# Project_Embedded_Lap_Counting.net
KiCad netlist of a schematic drawn in EAGLE
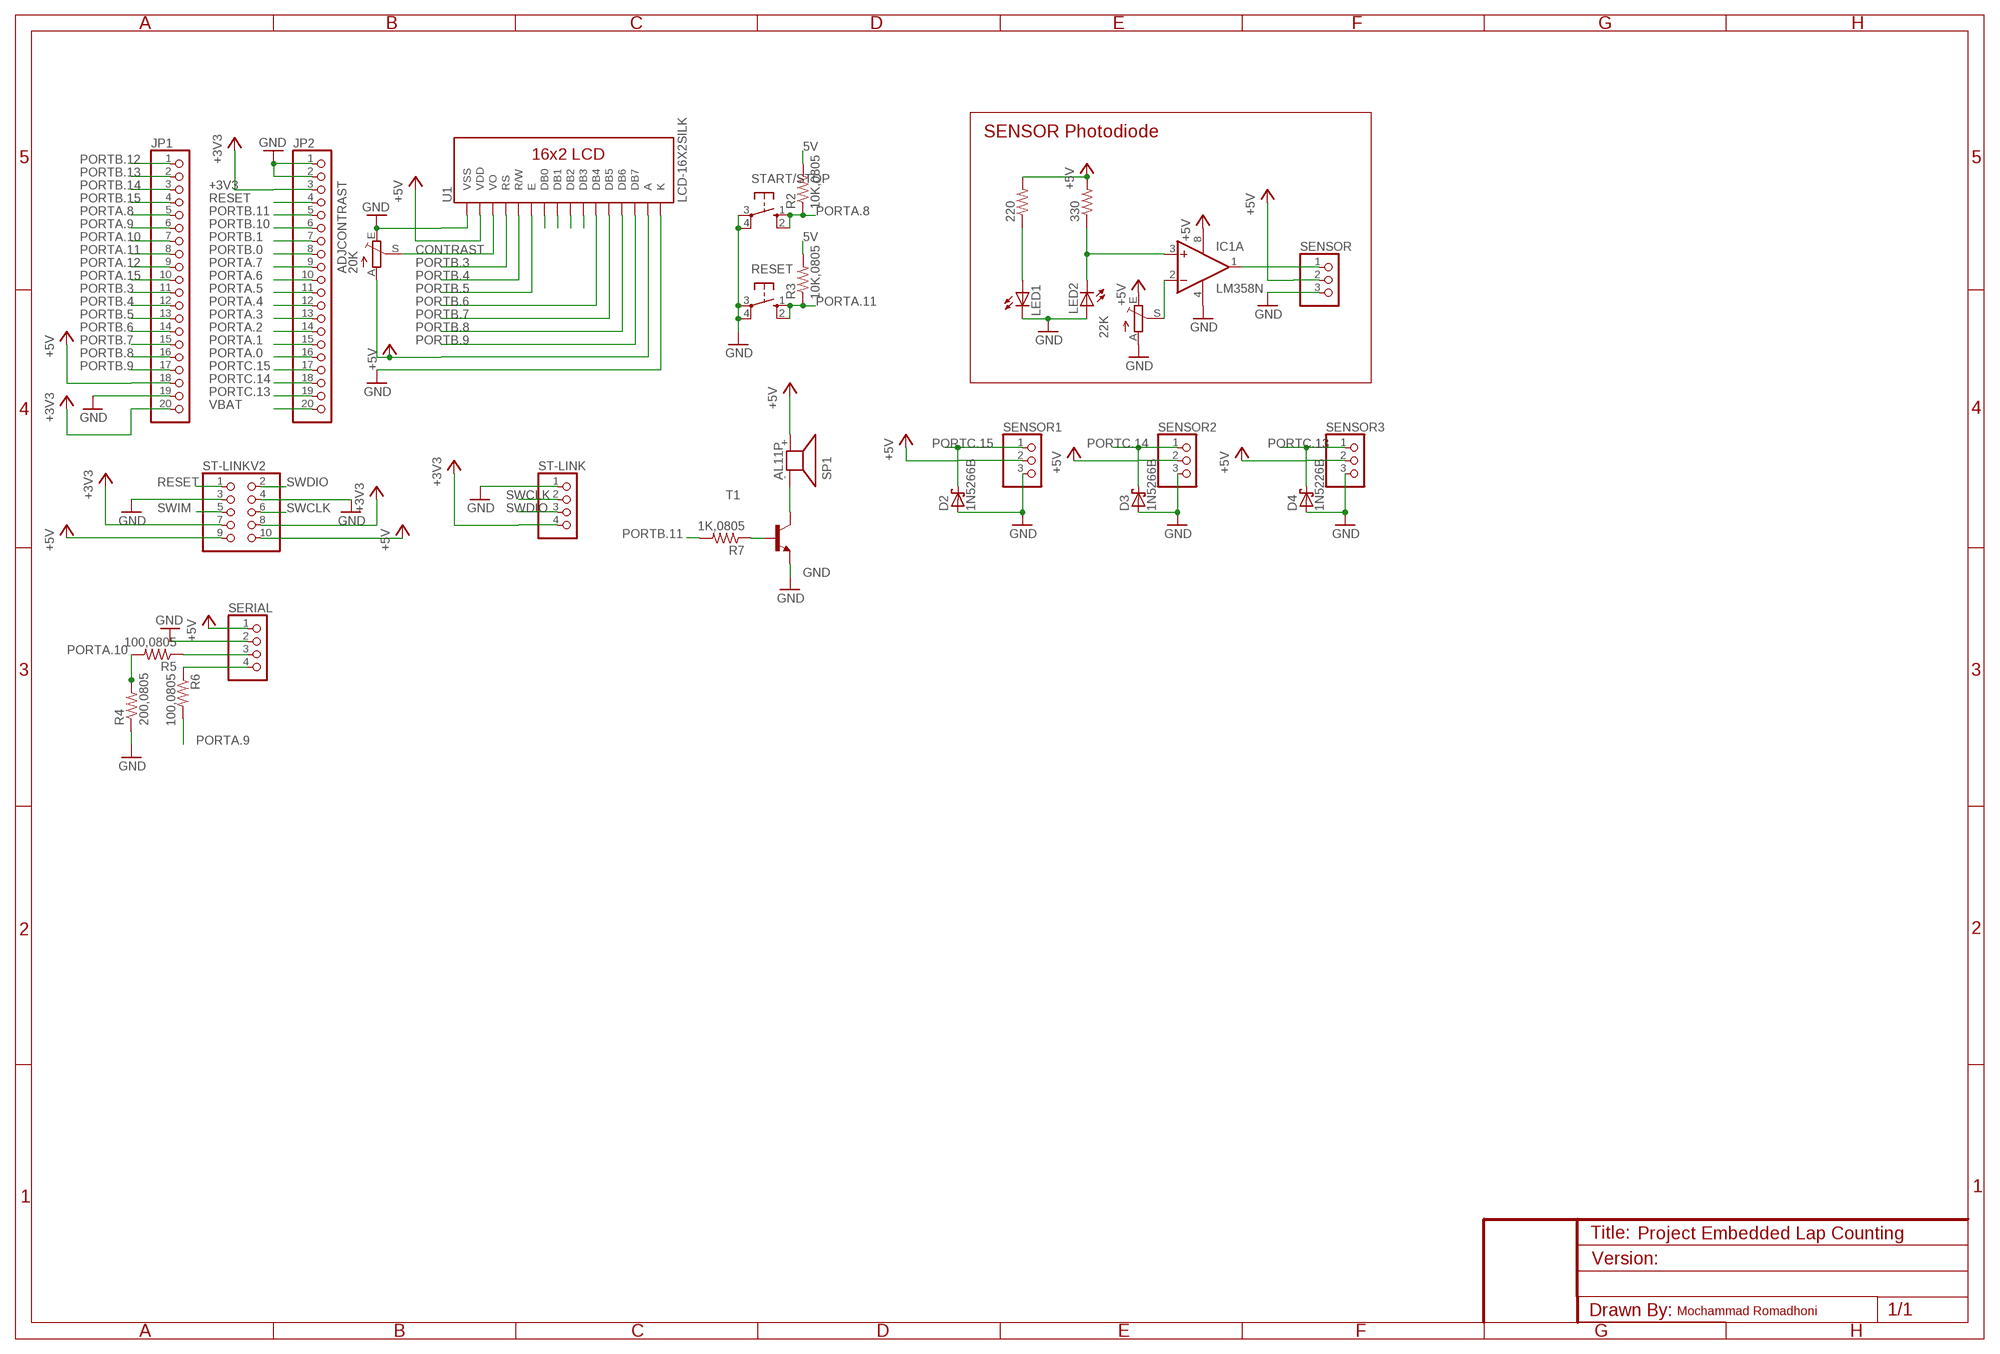
[diagram p0: schematic, sheet 1]

(export (version "E")
  (design (tool "Eeschema 10.0.6"))
  (components
    (comp (ref "22K")
      (value "TRIM_EU-CA6V")
      (footprint "eagle-import:CA6V")
      (libsource (lib "eagle-import") (part "TRIM_EU-CA6V"))
    )
    (comp (ref "220")
      (value "R-US_0204/7")
      (footprint "eagle-import:0204_7")
      (libsource (lib "eagle-import") (part "R-US_0204/7"))
    )
    (comp (ref "330")
      (value "R-US_0204/7")
      (footprint "eagle-import:0204_7")
      (libsource (lib "eagle-import") (part "R-US_0204/7"))
    )
    (comp (ref "ADJCONTRAST")
      (value "20K")
      (footprint "eagle-import:CA6V")
      (libsource (lib "eagle-import") (part "TRIM_EU-CA6V"))
    )
    (comp (ref "D2")
      (value "1N5266B")
      (footprint "eagle-import:DO35-10")
      (libsource (lib "eagle-import") (part "BAT42"))
    )
    (comp (ref "D3")
      (value "1N5266B")
      (footprint "eagle-import:DO35-10")
      (libsource (lib "eagle-import") (part "BAT42"))
    )
    (comp (ref "D4")
      (value "1N5226B")
      (footprint "eagle-import:DO35-10")
      (libsource (lib "eagle-import") (part "BAT42"))
    )
    (comp (ref "IC1")
      (value "LM358N")
      (footprint "eagle-import:DIL08")
      (libsource (lib "eagle-import") (part "LM358N"))
    )
    (comp (ref "JP1")
      (value "PINHD-1X20")
      (footprint "eagle-import:1X20")
      (libsource (lib "eagle-import") (part "PINHD-1X20"))
    )
    (comp (ref "JP2")
      (value "PINHD-1X20")
      (footprint "eagle-import:1X20")
      (libsource (lib "eagle-import") (part "PINHD-1X20"))
    )
    (comp (ref "LED1")
      (value "LED3MM")
      (footprint "eagle-import:LED3MM")
      (libsource (lib "eagle-import") (part "LED3MM"))
    )
    (comp (ref "LED2")
      (value "LED3MM")
      (footprint "eagle-import:LED3MM")
      (libsource (lib "eagle-import") (part "LED3MM"))
    )
    (comp (ref "R2")
      (value "10K,0805")
      (footprint "eagle-import:M0805")
      (libsource (lib "eagle-import") (part "R-US_M0805"))
    )
    (comp (ref "R3")
      (value "10K,0805")
      (footprint "eagle-import:M0805")
      (libsource (lib "eagle-import") (part "R-US_M0805"))
    )
    (comp (ref "R4")
      (value "200,0805")
      (footprint "eagle-import:M0805")
      (libsource (lib "eagle-import") (part "R-US_M0805"))
    )
    (comp (ref "R5")
      (value "100,0805")
      (footprint "eagle-import:M0805")
      (libsource (lib "eagle-import") (part "R-US_M0805"))
    )
    (comp (ref "R6")
      (value "100,0805")
      (footprint "eagle-import:M0805")
      (libsource (lib "eagle-import") (part "R-US_M0805"))
    )
    (comp (ref "R7")
      (value "1K,0805")
      (footprint "eagle-import:M0805")
      (libsource (lib "eagle-import") (part "R-US_M0805"))
    )
    (comp (ref "RESET")
      (value "40-XX")
      (footprint "eagle-import:B3F-40XX")
      (fields (field (name "MF") "OMRON COMPONENTS USA") (field (name "MPN") "B3F-4000"))
      (libsource (lib "eagle-import") (part "40-XX"))
    )
    (comp (ref "SENSOR")
      (value "PINHD-1X3")
      (footprint "eagle-import:1X03")
      (libsource (lib "eagle-import") (part "PINHD-1X3"))
    )
    (comp (ref "SENSOR1")
      (value "PINHD-1X3")
      (footprint "eagle-import:1X03")
      (libsource (lib "eagle-import") (part "PINHD-1X3"))
    )
    (comp (ref "SENSOR2")
      (value "PINHD-1X3")
      (footprint "eagle-import:1X03")
      (libsource (lib "eagle-import") (part "PINHD-1X3"))
    )
    (comp (ref "SENSOR3")
      (value "PINHD-1X3")
      (footprint "eagle-import:1X03")
      (libsource (lib "eagle-import") (part "PINHD-1X3"))
    )
    (comp (ref "SERIAL")
      (value "PINHD-1X4")
      (footprint "eagle-import:1X04")
      (libsource (lib "eagle-import") (part "PINHD-1X4"))
    )
    (comp (ref "SP1")
      (value "AL11P")
      (footprint "eagle-import:AL11P")
      (libsource (lib "eagle-import") (part "AL11P"))
    )
    (comp (ref "ST-LINK")
      (value "PINHD-1X4")
      (footprint "eagle-import:1X04")
      (libsource (lib "eagle-import") (part "PINHD-1X4"))
    )
    (comp (ref "ST-LINKV2")
      (value "PINHD-2X5")
      (footprint "eagle-import:2X05")
      (libsource (lib "eagle-import") (part "PINHD-2X5"))
    )
    (comp (ref "START/STOP")
      (value "40-XX")
      (footprint "eagle-import:B3F-40XX")
      (fields (field (name "MF") "OMRON COMPONENTS USA") (field (name "MPN") "B3F-4000"))
      (libsource (lib "eagle-import") (part "40-XX"))
    )
    (comp (ref "T1")
      (value "-NPN-SOT23-EBC")
      (footprint "eagle-import:SOT23-EBC")
      (libsource (lib "eagle-import") (part "-NPN-SOT23-EBC"))
    )
    (comp (ref "U1")
      (value "LCD-16X2SILK")
      (footprint "eagle-import:LCD-16X2")
      (libsource (lib "eagle-import") (part "LCD-16X2SILK"))
    )
  )
  (nets
    (net (code "1") (name "+3V3") (class "Default")
      (node (ref "JP1") (pin "20") (pinfunction "20_20") (pintype "passive"))
      (node (ref "JP2") (pin "3") (pinfunction "3_3") (pintype "passive"))
      (node (ref "ST-LINK") (pin "4") (pinfunction "4_4") (pintype "passive"))
      (node (ref "ST-LINKV2") (pin "7") (pinfunction "7_7") (pintype "passive"))
      (node (ref "ST-LINKV2") (pin "8") (pinfunction "8_8") (pintype "passive"))
    )
    (net (code "2") (name "+5V") (class "Default")
      (node (ref "220") (pin "2") (pinfunction "2_2") (pintype "passive"))
      (node (ref "22K") (pin "E") (pinfunction "E_E") (pintype "passive"))
      (node (ref "330") (pin "2") (pinfunction "2_2") (pintype "passive"))
      (node (ref "ADJCONTRAST") (pin "A") (pinfunction "A_A") (pintype "passive"))
      (node (ref "IC1") (pin "8") (pinfunction "V+_8") (pintype "power_in"))
      (node (ref "JP1") (pin "18") (pinfunction "18_18") (pintype "passive"))
      (node (ref "SENSOR") (pin "2") (pinfunction "2_2") (pintype "passive"))
      (node (ref "SENSOR1") (pin "2") (pinfunction "2_2") (pintype "passive"))
      (node (ref "SENSOR2") (pin "2") (pinfunction "2_2") (pintype "passive"))
      (node (ref "SENSOR3") (pin "2") (pinfunction "2_2") (pintype "passive"))
      (node (ref "SERIAL") (pin "1") (pinfunction "1_1") (pintype "passive"))
      (node (ref "SP1") (pin "+") (pinfunction "2_+") (pintype "passive"))
      (node (ref "ST-LINKV2") (pin "10") (pinfunction "10_10") (pintype "passive"))
      (node (ref "ST-LINKV2") (pin "9") (pinfunction "9_9") (pintype "passive"))
      (node (ref "U1") (pin "15") (pinfunction "A_15") (pintype "power_in"))
      (node (ref "U1") (pin "2") (pinfunction "VDD_2") (pintype "power_in"))
    )
    (net (code "3") (name "/5V") (class "Default")
      (node (ref "R2") (pin "2") (pinfunction "2_2") (pintype "passive"))
      (node (ref "R3") (pin "2") (pinfunction "2_2") (pintype "passive"))
    )
    (net (code "4") (name "/CONTRAST") (class "Default")
      (node (ref "ADJCONTRAST") (pin "S") (pinfunction "S_S") (pintype "passive"))
      (node (ref "U1") (pin "3") (pinfunction "VO_3") (pintype "bidirectional"))
    )
    (net (code "5") (name "/PORTA.0") (class "Default")
      (node (ref "JP2") (pin "16") (pinfunction "16_16") (pintype "passive"))
    )
    (net (code "6") (name "/PORTA.1") (class "Default")
      (node (ref "JP2") (pin "15") (pinfunction "15_15") (pintype "passive"))
    )
    (net (code "7") (name "/PORTA.2") (class "Default")
      (node (ref "JP2") (pin "14") (pinfunction "14_14") (pintype "passive"))
    )
    (net (code "8") (name "/PORTA.3") (class "Default")
      (node (ref "JP2") (pin "13") (pinfunction "13_13") (pintype "passive"))
    )
    (net (code "9") (name "/PORTA.4") (class "Default")
      (node (ref "JP2") (pin "12") (pinfunction "12_12") (pintype "passive"))
    )
    (net (code "10") (name "/PORTA.5") (class "Default")
      (node (ref "JP2") (pin "11") (pinfunction "11_11") (pintype "passive"))
    )
    (net (code "11") (name "/PORTA.6") (class "Default")
      (node (ref "JP2") (pin "10") (pinfunction "10_10") (pintype "passive"))
    )
    (net (code "12") (name "/PORTA.7") (class "Default")
      (node (ref "JP2") (pin "9") (pinfunction "9_9") (pintype "passive"))
    )
    (net (code "13") (name "/PORTA.8") (class "Default")
      (node (ref "JP1") (pin "5") (pinfunction "5_5") (pintype "passive"))
      (node (ref "R2") (pin "1") (pinfunction "1_1") (pintype "passive"))
      (node (ref "START/STOP") (pin "1") (pinfunction "S_1") (pintype "passive"))
      (node (ref "START/STOP") (pin "2") (pinfunction "S1_2") (pintype "passive"))
    )
    (net (code "14") (name "/PORTA.9") (class "Default")
      (node (ref "JP1") (pin "6") (pinfunction "6_6") (pintype "passive"))
      (node (ref "R6") (pin "2") (pinfunction "2_2") (pintype "passive"))
    )
    (net (code "15") (name "/PORTA.10") (class "Default")
      (node (ref "JP1") (pin "7") (pinfunction "7_7") (pintype "passive"))
      (node (ref "R4") (pin "2") (pinfunction "2_2") (pintype "passive"))
      (node (ref "R5") (pin "2") (pinfunction "2_2") (pintype "passive"))
    )
    (net (code "16") (name "/PORTA.11") (class "Default")
      (node (ref "JP1") (pin "8") (pinfunction "8_8") (pintype "passive"))
      (node (ref "R3") (pin "1") (pinfunction "1_1") (pintype "passive"))
      (node (ref "RESET") (pin "1") (pinfunction "S_1") (pintype "passive"))
      (node (ref "RESET") (pin "2") (pinfunction "S1_2") (pintype "passive"))
    )
    (net (code "17") (name "/PORTA.12") (class "Default")
      (node (ref "JP1") (pin "9") (pinfunction "9_9") (pintype "passive"))
    )
    (net (code "18") (name "/PORTA.15") (class "Default")
      (node (ref "JP1") (pin "10") (pinfunction "10_10") (pintype "passive"))
    )
    (net (code "19") (name "/PORTB.0") (class "Default")
      (node (ref "JP2") (pin "8") (pinfunction "8_8") (pintype "passive"))
    )
    (net (code "20") (name "/PORTB.1") (class "Default")
      (node (ref "JP2") (pin "7") (pinfunction "7_7") (pintype "passive"))
    )
    (net (code "21") (name "/PORTB.3") (class "Default")
      (node (ref "JP1") (pin "11") (pinfunction "11_11") (pintype "passive"))
      (node (ref "U1") (pin "4") (pinfunction "RS_4") (pintype "input"))
    )
    (net (code "22") (name "/PORTB.4") (class "Default")
      (node (ref "JP1") (pin "12") (pinfunction "12_12") (pintype "passive"))
      (node (ref "U1") (pin "5") (pinfunction "R/W_5") (pintype "input"))
    )
    (net (code "23") (name "/PORTB.5") (class "Default")
      (node (ref "JP1") (pin "13") (pinfunction "13_13") (pintype "passive"))
      (node (ref "U1") (pin "6") (pinfunction "E_6") (pintype "input"))
    )
    (net (code "24") (name "/PORTB.6") (class "Default")
      (node (ref "JP1") (pin "14") (pinfunction "14_14") (pintype "passive"))
      (node (ref "U1") (pin "11") (pinfunction "DB4_11") (pintype "bidirectional"))
    )
    (net (code "25") (name "/PORTB.7") (class "Default")
      (node (ref "JP1") (pin "15") (pinfunction "15_15") (pintype "passive"))
      (node (ref "U1") (pin "12") (pinfunction "DB5_12") (pintype "bidirectional"))
    )
    (net (code "26") (name "/PORTB.8") (class "Default")
      (node (ref "JP1") (pin "16") (pinfunction "16_16") (pintype "passive"))
      (node (ref "U1") (pin "13") (pinfunction "DB6_13") (pintype "bidirectional"))
    )
    (net (code "27") (name "/PORTB.9") (class "Default")
      (node (ref "JP1") (pin "17") (pinfunction "17_17") (pintype "passive"))
      (node (ref "U1") (pin "14") (pinfunction "DB7_14") (pintype "bidirectional"))
    )
    (net (code "28") (name "/PORTB.10") (class "Default")
      (node (ref "JP2") (pin "6") (pinfunction "6_6") (pintype "passive"))
    )
    (net (code "29") (name "/PORTB.11") (class "Default")
      (node (ref "JP2") (pin "5") (pinfunction "5_5") (pintype "passive"))
      (node (ref "R7") (pin "2") (pinfunction "2_2") (pintype "passive"))
    )
    (net (code "30") (name "/PORTB.12") (class "Default")
      (node (ref "JP1") (pin "1") (pinfunction "1_1") (pintype "passive"))
    )
    (net (code "31") (name "/PORTB.13") (class "Default")
      (node (ref "JP1") (pin "2") (pinfunction "2_2") (pintype "passive"))
    )
    (net (code "32") (name "/PORTB.14") (class "Default")
      (node (ref "JP1") (pin "3") (pinfunction "3_3") (pintype "passive"))
    )
    (net (code "33") (name "/PORTB.15") (class "Default")
      (node (ref "JP1") (pin "4") (pinfunction "4_4") (pintype "passive"))
    )
    (net (code "34") (name "/PORTC.13") (class "Default")
      (node (ref "D4") (pin "C") (pinfunction "C_C") (pintype "passive"))
      (node (ref "JP2") (pin "19") (pinfunction "19_19") (pintype "passive"))
      (node (ref "SENSOR3") (pin "1") (pinfunction "1_1") (pintype "passive"))
    )
    (net (code "35") (name "/PORTC.14") (class "Default")
      (node (ref "D3") (pin "C") (pinfunction "C_C") (pintype "passive"))
      (node (ref "JP2") (pin "18") (pinfunction "18_18") (pintype "passive"))
      (node (ref "SENSOR2") (pin "1") (pinfunction "1_1") (pintype "passive"))
    )
    (net (code "36") (name "/PORTC.15") (class "Default")
      (node (ref "D2") (pin "C") (pinfunction "C_C") (pintype "passive"))
      (node (ref "JP2") (pin "17") (pinfunction "17_17") (pintype "passive"))
      (node (ref "SENSOR1") (pin "1") (pinfunction "1_1") (pintype "passive"))
    )
    (net (code "37") (name "/RESET") (class "Default")
      (node (ref "JP2") (pin "4") (pinfunction "4_4") (pintype "passive"))
      (node (ref "ST-LINKV2") (pin "1") (pinfunction "1_1") (pintype "passive"))
    )
    (net (code "38") (name "/SWCLK") (class "Default")
      (node (ref "ST-LINK") (pin "2") (pinfunction "2_2") (pintype "passive"))
      (node (ref "ST-LINKV2") (pin "6") (pinfunction "6_6") (pintype "passive"))
    )
    (net (code "39") (name "/SWDIO") (class "Default")
      (node (ref "ST-LINK") (pin "3") (pinfunction "3_3") (pintype "passive"))
      (node (ref "ST-LINKV2") (pin "2") (pinfunction "2_2") (pintype "passive"))
    )
    (net (code "40") (name "/SWIM") (class "Default")
      (node (ref "ST-LINKV2") (pin "5") (pinfunction "5_5") (pintype "passive"))
    )
    (net (code "41") (name "/VBAT") (class "Default")
      (node (ref "JP2") (pin "20") (pinfunction "20_20") (pintype "passive"))
    )
    (net (code "42") (name "GND") (class "Default")
      (node (ref "22K") (pin "A") (pinfunction "A_A") (pintype "passive"))
      (node (ref "ADJCONTRAST") (pin "E") (pinfunction "E_E") (pintype "passive"))
      (node (ref "D2") (pin "A") (pinfunction "A_A") (pintype "passive"))
      (node (ref "D3") (pin "A") (pinfunction "A_A") (pintype "passive"))
      (node (ref "D4") (pin "A") (pinfunction "A_A") (pintype "passive"))
      (node (ref "IC1") (pin "4") (pinfunction "V-_4") (pintype "power_in"))
      (node (ref "JP1") (pin "19") (pinfunction "19_19") (pintype "passive"))
      (node (ref "JP2") (pin "1") (pinfunction "1_1") (pintype "passive"))
      (node (ref "JP2") (pin "2") (pinfunction "2_2") (pintype "passive"))
      (node (ref "LED1") (pin "K") (pinfunction "C_K") (pintype "passive"))
      (node (ref "LED2") (pin "A") (pinfunction "A_A") (pintype "passive"))
      (node (ref "R4") (pin "1") (pinfunction "1_1") (pintype "passive"))
      (node (ref "RESET") (pin "3") (pinfunction "P_3") (pintype "passive"))
      (node (ref "RESET") (pin "4") (pinfunction "P1_4") (pintype "passive"))
      (node (ref "SENSOR") (pin "3") (pinfunction "3_3") (pintype "passive"))
      (node (ref "SENSOR1") (pin "3") (pinfunction "3_3") (pintype "passive"))
      (node (ref "SENSOR2") (pin "3") (pinfunction "3_3") (pintype "passive"))
      (node (ref "SENSOR3") (pin "3") (pinfunction "3_3") (pintype "passive"))
      (node (ref "SERIAL") (pin "2") (pinfunction "2_2") (pintype "passive"))
      (node (ref "ST-LINK") (pin "1") (pinfunction "1_1") (pintype "passive"))
      (node (ref "ST-LINKV2") (pin "3") (pinfunction "3_3") (pintype "passive"))
      (node (ref "ST-LINKV2") (pin "4") (pinfunction "4_4") (pintype "passive"))
      (node (ref "START/STOP") (pin "3") (pinfunction "P_3") (pintype "passive"))
      (node (ref "START/STOP") (pin "4") (pinfunction "P1_4") (pintype "passive"))
      (node (ref "T1") (pin "E") (pinfunction "E_E") (pintype "passive"))
      (node (ref "U1") (pin "1") (pinfunction "VSS_1") (pintype "power_in"))
      (node (ref "U1") (pin "16") (pinfunction "K_16") (pintype "power_in"))
    )
    (net (code "43") (name "Net-(220-Pad1)") (class "Default")
      (node (ref "220") (pin "1") (pinfunction "1_1") (pintype "passive"))
      (node (ref "LED1") (pin "A") (pinfunction "A_A") (pintype "passive"))
    )
    (net (code "44") (name "Net-(IC1A-+IN)") (class "Default")
      (node (ref "330") (pin "1") (pinfunction "1_1") (pintype "passive"))
      (node (ref "IC1") (pin "3") (pinfunction "+IN_3") (pintype "input"))
      (node (ref "LED2") (pin "K") (pinfunction "C_K") (pintype "passive"))
    )
    (net (code "45") (name "Net-(IC1A--IN)") (class "Default")
      (node (ref "22K") (pin "S") (pinfunction "S_S") (pintype "passive"))
      (node (ref "IC1") (pin "2") (pinfunction "-IN_2") (pintype "input"))
    )
    (net (code "46") (name "Net-(IC1A-OUT)") (class "Default")
      (node (ref "IC1") (pin "1") (pinfunction "OUT_1") (pintype "output"))
      (node (ref "SENSOR") (pin "1") (pinfunction "1_1") (pintype "passive"))
    )
    (net (code "47") (name "Net-(R5-Pad1)") (class "Default")
      (node (ref "R5") (pin "1") (pinfunction "1_1") (pintype "passive"))
      (node (ref "SERIAL") (pin "3") (pinfunction "3_3") (pintype "passive"))
    )
    (net (code "48") (name "Net-(R6-Pad1)") (class "Default")
      (node (ref "R6") (pin "1") (pinfunction "1_1") (pintype "passive"))
      (node (ref "SERIAL") (pin "4") (pinfunction "4_4") (pintype "passive"))
    )
    (net (code "49") (name "Net-(R7-Pad1)") (class "Default")
      (node (ref "R7") (pin "1") (pinfunction "1_1") (pintype "passive"))
      (node (ref "T1") (pin "B") (pinfunction "B_B") (pintype "passive"))
    )
    (net (code "50") (name "Net-(SP1-1)") (class "Default")
      (node (ref "SP1") (pin "-") (pinfunction "1_-") (pintype "passive"))
      (node (ref "T1") (pin "C") (pinfunction "C_C") (pintype "passive"))
    )
    (net (code "51") (name "unconnected-(U1-DB0-Pad7)") (class "Default")
      (node (ref "U1") (pin "7") (pinfunction "DB0_7") (pintype "bidirectional"))
    )
    (net (code "52") (name "unconnected-(U1-DB1-Pad8)") (class "Default")
      (node (ref "U1") (pin "8") (pinfunction "DB1_8") (pintype "bidirectional"))
    )
    (net (code "53") (name "unconnected-(U1-DB2-Pad9)") (class "Default")
      (node (ref "U1") (pin "9") (pinfunction "DB2_9") (pintype "bidirectional"))
    )
    (net (code "54") (name "unconnected-(U1-DB3-Pad10)") (class "Default")
      (node (ref "U1") (pin "10") (pinfunction "DB3_10") (pintype "bidirectional"))
    )
  )
)
